# SlotCarControllerRev0.net
KiCad netlist of a schematic drawn in Altium Designer
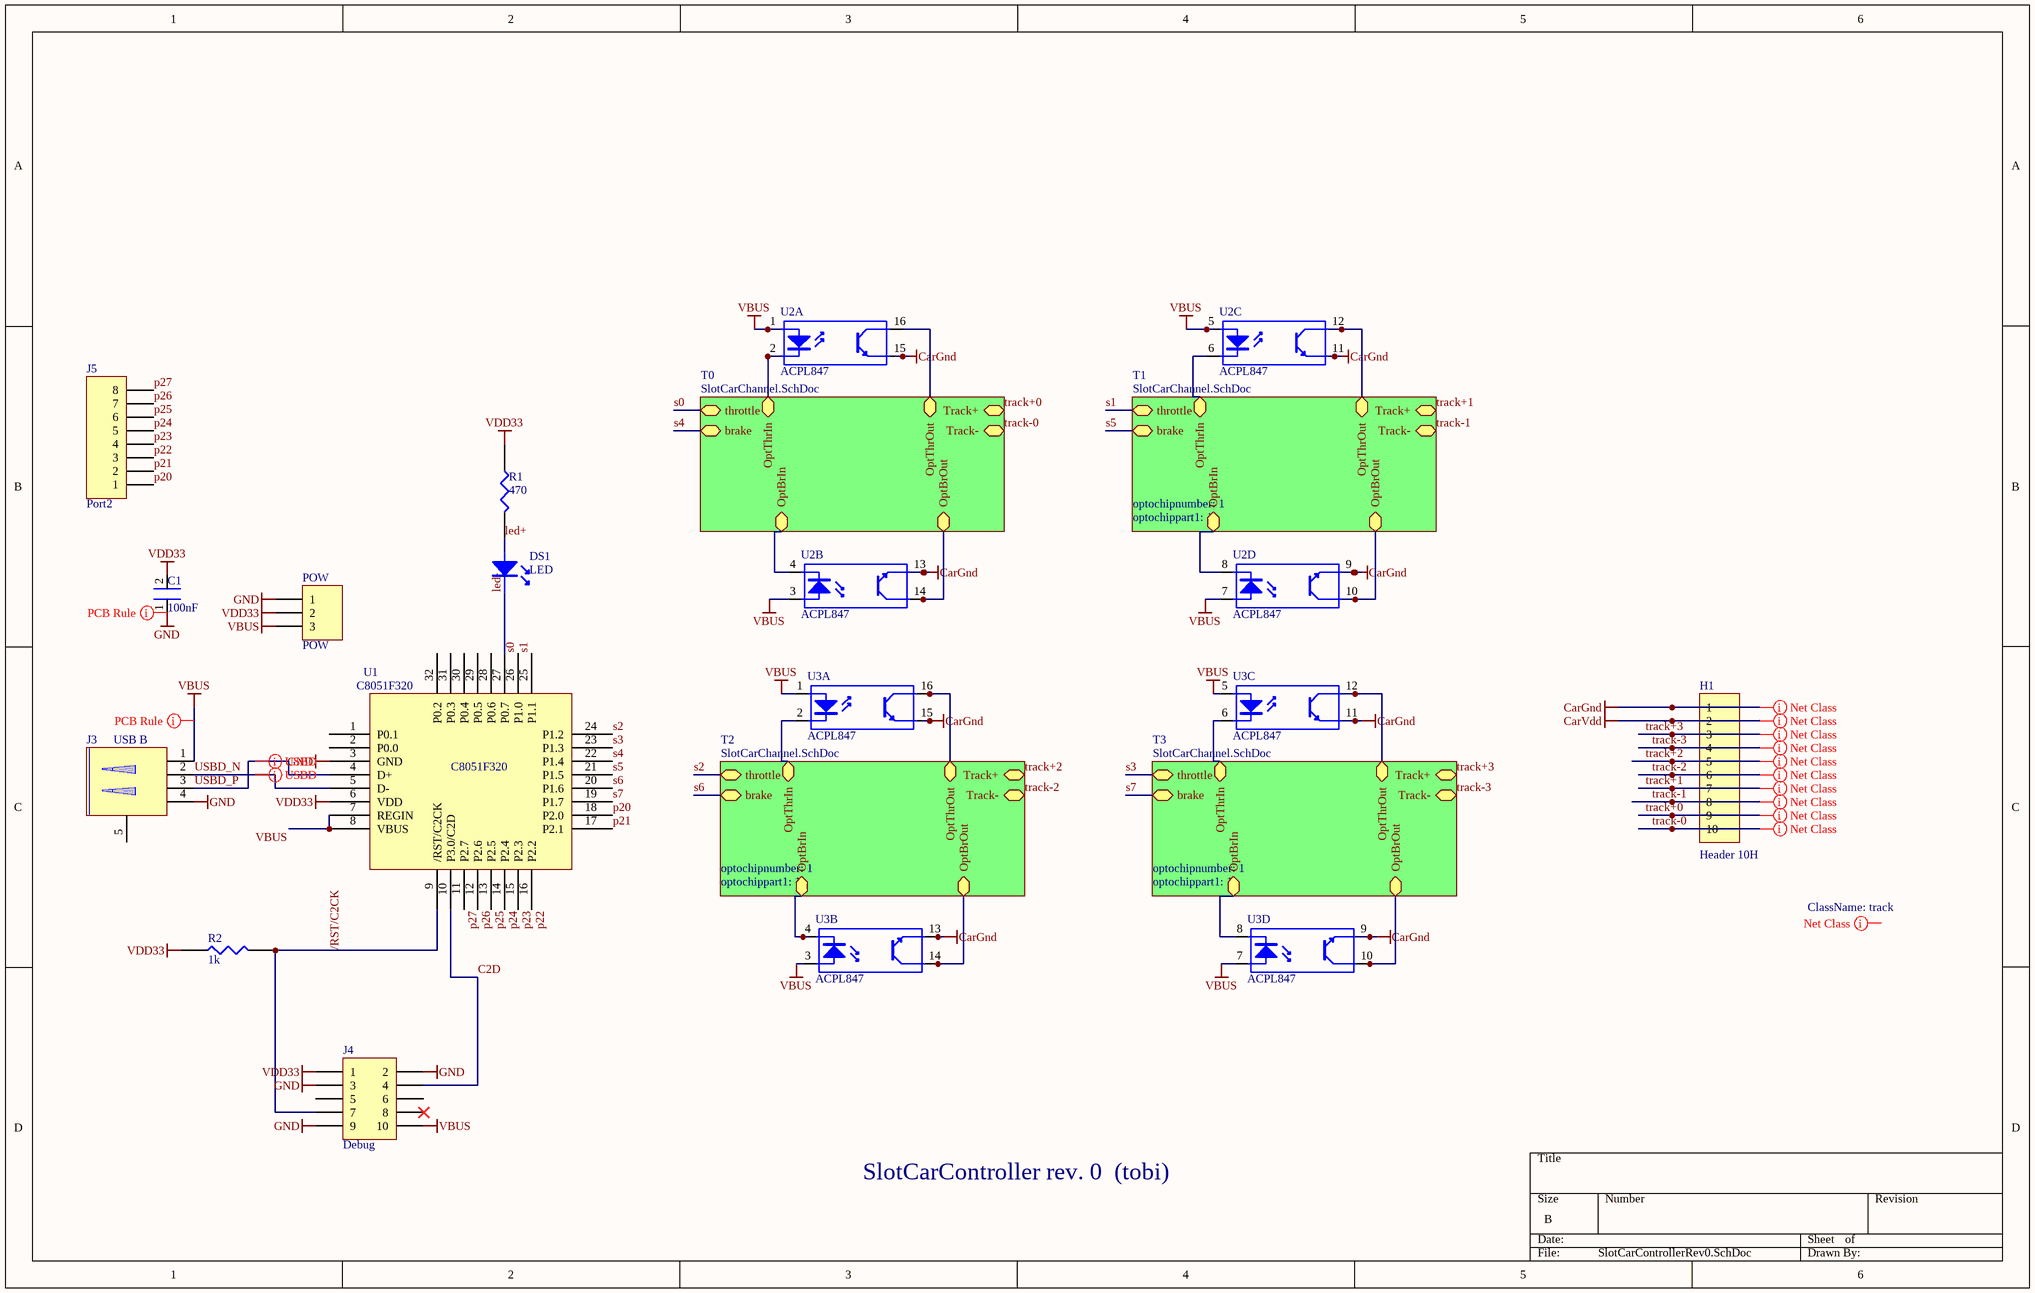
[diagram p0: SlotCarControllerRev0.SchDoc]

(export (version "E")
  (design (tool "Eeschema 10.0.6"))
  (components
    (comp (ref "C1")
      (value "100nF")
      (footprint "CC1608-0603")
      (libsource (lib "tobi SCHEMATIC") (part "CAPCHIP"))
    )
    (comp (ref "DS1")
      (value "LED")
      (footprint "0805LED")
      (description "LED, SMT 3mm by 1.5mm")
      (libsource (lib "SimpleMonitorUSBAER") (part "LED"))
    )
    (comp (ref "H1")
      (value "Header 10H")
      (footprint "SL508/10/90")
      (description "Header, 10-Pin, Right Angle")
      (fields (field (name "PUBLISHER") "Altium Limited"))
      (libsource (lib "Miscellaneous Connectors") (part "Header 10H"))
    )
    (comp (ref "J3")
      (value "USB B")
      (footprint "usb")
      (description "USB TypB")
      (libsource (lib "DAC") (part "USB"))
    )
    (comp (ref "J4")
      (value "Debug")
      (footprint "HDR2X5")
      (description "Header, 5-Pin, Dual row")
      (fields (field (name "PUBLISHER") "Altium Limited"))
      (libsource (lib "Miscellaneous Connectors") (part "Header 5X2"))
    )
    (comp (ref "J5")
      (value "Port2")
      (footprint "HDR1X8")
      (description "Header, 8-Pin")
      (fields (field (name "PUBLISHER") "Altium Limited"))
      (libsource (lib "Miscellaneous Connectors") (part "Header 8"))
    )
    (comp (ref "POW")
      (value "POW")
      (footprint "HDR1X3")
      (description "Header, 3-Pin")
      (fields (field (name "PUBLISHER") "Altium Limited"))
      (libsource (lib "Miscellaneous Connectors") (part "Header 3"))
    )
    (comp (ref "R1") (value "470") (footprint "CR1608-0603") (libsource (lib "*") (part "RES1")))
    (comp (ref "R2") (value "1k") (footprint "CR1608-0603") (libsource (lib "*") (part "RES1")))
    (comp (ref "U1")
      (value "C8051F320")
      (footprint "TQFP32")
      (description "Silicon Labs USB Microcontroller")
      (libsource (lib "tobi SCHEMATIC") (part "C8051F320"))
    )
    (comp (ref "U2")
      (value "ACPL847")
      (footprint "DIP16")
      (description "16-Pin 4-channel Phototransistor Optocoupler")
      (fields (field (name "PUBLISHER") "tobi"))
      (libsource (lib "SlotCarController") (part "Opto16"))
    )
    (comp (ref "U3")
      (value "ACPL847")
      (footprint "DIP16")
      (description "16-Pin 4-channel Phototransistor Optocoupler")
      (fields (field (name "PUBLISHER") "tobi"))
      (libsource (lib "SlotCarController") (part "Opto16"))
    )
  )
  (nets
    (net (code "1") (name "/C2D") (class "Default")
      (node (ref "J4") (pin "4") (pinfunction "4_4") (pintype "passive"))
      (node (ref "U1") (pin "10") (pinfunction "P3.0/C2D_10") (pintype "passive"))
    )
    (net (code "2") (name "/OptBrIn") (class "Default")
      (node (ref "U3") (pin "8") (pinfunction "8_8") (pintype "passive"))
    )
    (net (code "3") (name "/OptBrIn_1") (class "Default")
      (node (ref "U2") (pin "8") (pinfunction "8_8") (pintype "passive"))
    )
    (net (code "4") (name "/OptBrIn_2") (class "Default")
      (node (ref "U2") (pin "4") (pinfunction "4_4") (pintype "passive"))
    )
    (net (code "5") (name "/OptBrIn_3") (class "Default")
      (node (ref "U3") (pin "4") (pinfunction "4_4") (pintype "passive"))
    )
    (net (code "6") (name "/OptBrOut") (class "Default")
      (node (ref "U3") (pin "10") (pinfunction "10_10") (pintype "passive"))
    )
    (net (code "7") (name "/OptBrOut_1") (class "Default")
      (node (ref "U2") (pin "10") (pinfunction "10_10") (pintype "passive"))
    )
    (net (code "8") (name "/OptBrOut_2") (class "Default")
      (node (ref "U2") (pin "14") (pinfunction "14_14") (pintype "passive"))
    )
    (net (code "9") (name "/OptBrOut_3") (class "Default")
      (node (ref "U3") (pin "14") (pinfunction "14_14") (pintype "passive"))
    )
    (net (code "10") (name "/OptThrIn") (class "Default")
      (node (ref "U2") (pin "2") (pinfunction "K_2") (pintype "passive"))
    )
    (net (code "11") (name "/OptThrIn_1") (class "Default")
      (node (ref "U2") (pin "6") (pinfunction "6_6") (pintype "passive"))
    )
    (net (code "12") (name "/OptThrIn_2") (class "Default")
      (node (ref "U3") (pin "6") (pinfunction "6_6") (pintype "passive"))
    )
    (net (code "13") (name "/OptThrIn_3") (class "Default")
      (node (ref "U3") (pin "2") (pinfunction "K_2") (pintype "passive"))
    )
    (net (code "14") (name "/OptThrOut") (class "Default")
      (node (ref "U2") (pin "16") (pinfunction "16_16") (pintype "passive"))
    )
    (net (code "15") (name "/OptThrOut_1") (class "Default")
      (node (ref "U3") (pin "12") (pinfunction "12_12") (pintype "passive"))
    )
    (net (code "16") (name "/OptThrOut_2") (class "Default")
      (node (ref "U2") (pin "12") (pinfunction "12_12") (pintype "passive"))
    )
    (net (code "17") (name "/OptThrOut_3") (class "Default")
      (node (ref "U3") (pin "16") (pinfunction "16_16") (pintype "passive"))
    )
    (net (code "18") (name "/USBD_N") (class "Default")
      (node (ref "J3") (pin "2") (pintype "passive"))
      (node (ref "U1") (pin "5") (pinfunction "D-_5") (pintype "passive"))
    )
    (net (code "19") (name "/USBD_P") (class "Default")
      (node (ref "J3") (pin "3") (pintype "passive"))
      (node (ref "U1") (pin "4") (pinfunction "D+_4") (pintype "passive"))
    )
    (net (code "20") (name "/led+") (class "Default")
      (node (ref "DS1") (pin "+") (pinfunction "1_+") (pintype "passive"))
      (node (ref "R1") (pin "2") (pinfunction "2_2") (pintype "passive"))
    )
    (net (code "21") (name "/led-") (class "Default")
      (node (ref "DS1") (pin "-") (pinfunction "2_-") (pintype "passive"))
      (node (ref "U1") (pin "27") (pinfunction "P0.7_27") (pintype "passive"))
    )
    (net (code "22") (name "/p20") (class "Default")
      (node (ref "J5") (pin "1") (pinfunction "1_1") (pintype "passive"))
      (node (ref "U1") (pin "18") (pinfunction "P2.0_18") (pintype "passive"))
    )
    (net (code "23") (name "/p21") (class "Default")
      (node (ref "J5") (pin "2") (pinfunction "2_2") (pintype "passive"))
      (node (ref "U1") (pin "17") (pinfunction "P2.1_17") (pintype "passive"))
    )
    (net (code "24") (name "/p22") (class "Default")
      (node (ref "J5") (pin "3") (pinfunction "3_3") (pintype "passive"))
      (node (ref "U1") (pin "16") (pinfunction "P2.2_16") (pintype "passive"))
    )
    (net (code "25") (name "/p23") (class "Default")
      (node (ref "J5") (pin "4") (pinfunction "4_4") (pintype "passive"))
      (node (ref "U1") (pin "15") (pinfunction "P2.3_15") (pintype "passive"))
    )
    (net (code "26") (name "/p24") (class "Default")
      (node (ref "J5") (pin "5") (pinfunction "5_5") (pintype "passive"))
      (node (ref "U1") (pin "14") (pinfunction "P2.4_14") (pintype "passive"))
    )
    (net (code "27") (name "/p25") (class "Default")
      (node (ref "J5") (pin "6") (pinfunction "6_6") (pintype "passive"))
      (node (ref "U1") (pin "13") (pinfunction "P2.5_13") (pintype "passive"))
    )
    (net (code "28") (name "/p26") (class "Default")
      (node (ref "J5") (pin "7") (pinfunction "7_7") (pintype "passive"))
      (node (ref "U1") (pin "12") (pinfunction "P2.6_12") (pintype "passive"))
    )
    (net (code "29") (name "/p27") (class "Default")
      (node (ref "J5") (pin "8") (pinfunction "8_8") (pintype "passive"))
      (node (ref "U1") (pin "11") (pinfunction "P2.7_11") (pintype "passive"))
    )
    (net (code "30") (name "/s0") (class "Default")
      (node (ref "U1") (pin "26") (pinfunction "P1.0_26") (pintype "passive"))
    )
    (net (code "31") (name "/s1") (class "Default")
      (node (ref "U1") (pin "25") (pinfunction "P1.1_25") (pintype "passive"))
    )
    (net (code "32") (name "/s2") (class "Default")
      (node (ref "U1") (pin "24") (pinfunction "P1.2_24") (pintype "passive"))
    )
    (net (code "33") (name "/s3") (class "Default")
      (node (ref "U1") (pin "23") (pinfunction "P1.3_23") (pintype "passive"))
    )
    (net (code "34") (name "/s4") (class "Default")
      (node (ref "U1") (pin "22") (pinfunction "P1.4_22") (pintype "passive"))
    )
    (net (code "35") (name "/s5") (class "Default")
      (node (ref "U1") (pin "21") (pinfunction "P1.5_21") (pintype "passive"))
    )
    (net (code "36") (name "/s6") (class "Default")
      (node (ref "U1") (pin "20") (pinfunction "P1.6_20") (pintype "passive"))
    )
    (net (code "37") (name "/s7") (class "Default")
      (node (ref "U1") (pin "19") (pinfunction "P1.7_19") (pintype "passive"))
    )
    (net (code "38") (name "/track+0") (class "Default")
      (node (ref "H1") (pin "9") (pinfunction "9_9") (pintype "passive"))
    )
    (net (code "39") (name "/track+1") (class "Default")
      (node (ref "H1") (pin "7") (pinfunction "7_7") (pintype "passive"))
    )
    (net (code "40") (name "/track+2") (class "Default")
      (node (ref "H1") (pin "5") (pinfunction "5_5") (pintype "passive"))
    )
    (net (code "41") (name "/track+3") (class "Default")
      (node (ref "H1") (pin "3") (pinfunction "3_3") (pintype "passive"))
    )
    (net (code "42") (name "/track-0") (class "Default")
      (node (ref "H1") (pin "10") (pinfunction "10_10") (pintype "passive"))
    )
    (net (code "43") (name "/track-1") (class "Default")
      (node (ref "H1") (pin "8") (pinfunction "8_8") (pintype "passive"))
    )
    (net (code "44") (name "/track-2") (class "Default")
      (node (ref "H1") (pin "6") (pinfunction "6_6") (pintype "passive"))
    )
    (net (code "45") (name "/track-3") (class "Default")
      (node (ref "H1") (pin "4") (pinfunction "4_4") (pintype "passive"))
    )
    (net (code "46") (name "/{slash}RST{slash}C2CK") (class "Default")
      (node (ref "J4") (pin "7") (pinfunction "7_7") (pintype "passive"))
      (node (ref "R2") (pin "2") (pinfunction "2_2") (pintype "passive"))
      (node (ref "U1") (pin "9") (pinfunction "/RST/C2CK_9") (pintype "passive"))
    )
    (net (code "47") (name "CarGnd") (class "Default")
      (node (ref "H1") (pin "1") (pinfunction "1_1") (pintype "passive"))
      (node (ref "U2") (pin "11") (pinfunction "11_11") (pintype "passive"))
      (node (ref "U2") (pin "13") (pinfunction "13_13") (pintype "passive"))
      (node (ref "U2") (pin "15") (pinfunction "15_15") (pintype "passive"))
      (node (ref "U2") (pin "9") (pinfunction "9_9") (pintype "passive"))
      (node (ref "U3") (pin "11") (pinfunction "11_11") (pintype "passive"))
      (node (ref "U3") (pin "13") (pinfunction "13_13") (pintype "passive"))
      (node (ref "U3") (pin "15") (pinfunction "15_15") (pintype "passive"))
      (node (ref "U3") (pin "9") (pinfunction "9_9") (pintype "passive"))
    )
    (net (code "48") (name "CarVdd") (class "Default")
      (node (ref "H1") (pin "2") (pinfunction "2_2") (pintype "passive"))
    )
    (net (code "49") (name "GND") (class "Default")
      (node (ref "C1") (pin "1") (pintype "passive"))
      (node (ref "J3") (pin "4") (pintype "passive"))
      (node (ref "J4") (pin "2") (pinfunction "2_2") (pintype "passive"))
      (node (ref "J4") (pin "3") (pinfunction "3_3") (pintype "passive"))
      (node (ref "J4") (pin "9") (pinfunction "9_9") (pintype "passive"))
      (node (ref "POW") (pin "1") (pinfunction "1_1") (pintype "passive"))
      (node (ref "U1") (pin "3") (pinfunction "GND_3") (pintype "passive"))
    )
    (net (code "50") (name "VBUS") (class "Default")
      (node (ref "J3") (pin "1") (pintype "passive"))
      (node (ref "J4") (pin "10") (pinfunction "10_10") (pintype "passive"))
      (node (ref "POW") (pin "3") (pinfunction "3_3") (pintype "passive"))
      (node (ref "U1") (pin "7") (pinfunction "REGIN_7") (pintype "passive"))
      (node (ref "U1") (pin "8") (pinfunction "VBUS_8") (pintype "passive"))
      (node (ref "U2") (pin "1") (pinfunction "A_1") (pintype "passive"))
      (node (ref "U2") (pin "3") (pinfunction "3_3") (pintype "passive"))
      (node (ref "U2") (pin "5") (pinfunction "5_5") (pintype "passive"))
      (node (ref "U2") (pin "7") (pinfunction "7_7") (pintype "passive"))
      (node (ref "U3") (pin "1") (pinfunction "A_1") (pintype "passive"))
      (node (ref "U3") (pin "3") (pinfunction "3_3") (pintype "passive"))
      (node (ref "U3") (pin "5") (pinfunction "5_5") (pintype "passive"))
      (node (ref "U3") (pin "7") (pinfunction "7_7") (pintype "passive"))
    )
    (net (code "51") (name "VDD33") (class "Default")
      (node (ref "C1") (pin "2") (pintype "passive"))
      (node (ref "J4") (pin "1") (pinfunction "1_1") (pintype "passive"))
      (node (ref "POW") (pin "2") (pinfunction "2_2") (pintype "passive"))
      (node (ref "R1") (pin "1") (pinfunction "1_1") (pintype "passive"))
      (node (ref "R2") (pin "1") (pinfunction "1_1") (pintype "passive"))
      (node (ref "U1") (pin "6") (pinfunction "VDD_6") (pintype "passive"))
    )
    (net (code "52") (name "unconnected-(J3-Pad5)") (class "Default")
      (node (ref "J3") (pin "5") (pintype "passive"))
    )
    (net (code "53") (name "unconnected-(J4-Pad5)") (class "Default")
      (node (ref "J4") (pin "5") (pinfunction "5_5") (pintype "passive"))
    )
    (net (code "54") (name "unconnected-(J4-Pad6)") (class "Default")
      (node (ref "J4") (pin "6") (pinfunction "6_6") (pintype "passive"))
    )
    (net (code "55") (name "unconnected-(J4-Pad8)") (class "Default")
      (node (ref "J4") (pin "8") (pinfunction "8_8") (pintype "passive+no_connect"))
    )
    (net (code "56") (name "unconnected-(U1-P0.0-Pad2)") (class "Default")
      (node (ref "U1") (pin "2") (pinfunction "P0.0_2") (pintype "passive"))
    )
    (net (code "57") (name "unconnected-(U1-P0.1-Pad1)") (class "Default")
      (node (ref "U1") (pin "1") (pinfunction "P0.1_1") (pintype "passive"))
    )
    (net (code "58") (name "unconnected-(U1-P0.2-Pad32)") (class "Default")
      (node (ref "U1") (pin "32") (pinfunction "P0.2_32") (pintype "passive"))
    )
    (net (code "59") (name "unconnected-(U1-P0.3-Pad31)") (class "Default")
      (node (ref "U1") (pin "31") (pinfunction "P0.3_31") (pintype "passive"))
    )
    (net (code "60") (name "unconnected-(U1-P0.4-Pad30)") (class "Default")
      (node (ref "U1") (pin "30") (pinfunction "P0.4_30") (pintype "passive"))
    )
    (net (code "61") (name "unconnected-(U1-P0.5-Pad29)") (class "Default")
      (node (ref "U1") (pin "29") (pinfunction "P0.5_29") (pintype "passive"))
    )
    (net (code "62") (name "unconnected-(U1-P0.6-Pad28)") (class "Default")
      (node (ref "U1") (pin "28") (pinfunction "P0.6_28") (pintype "passive"))
    )
  )
)
